# PreAmplifier.net
KiCad netlist of a schematic drawn in Altium Designer
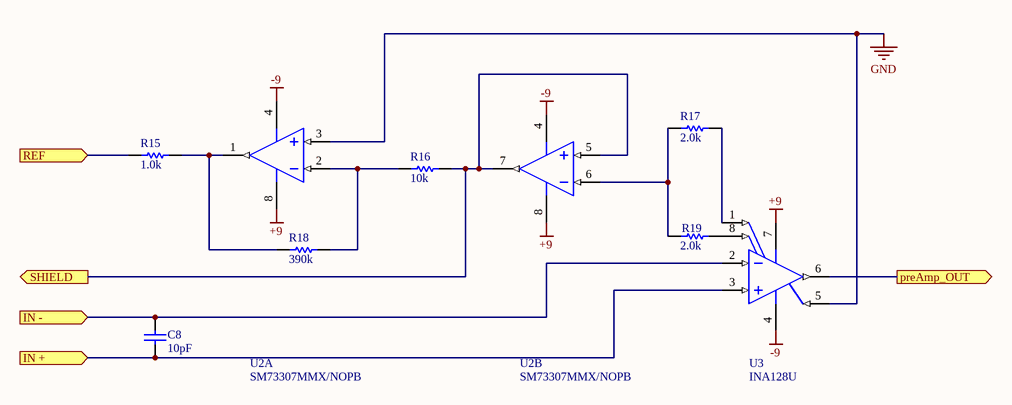
[diagram p0: PreAmplifier.SchDoc]

(export (version "E")
  (design (tool "Eeschema 10.0.6"))
  (components
    (comp (ref "C8")
      (value "10pF")
      (footprint "0402cap")
      (description "0402 Ceramic Chip Capacitor - Standard")
      (fields (field (name "Comment") "C0402"))
      (libsource (lib "Standard Components") (part "C0402"))
    )
    (comp (ref "R15")
      (value "1.0k")
      (footprint "0402RES")
      (description "0402 Chip Resistor - Standard")
      (fields (field (name "Comment") "R0402"))
      (libsource (lib "Standard Components") (part "R0402"))
    )
    (comp (ref "R16")
      (value "10k")
      (footprint "0402RES")
      (description "0402 Chip Resistor - Standard")
      (fields (field (name "Comment") "R0402"))
      (libsource (lib "Standard Components") (part "R0402"))
    )
    (comp (ref "R17")
      (value "2.0k")
      (footprint "0402RES")
      (description "0402 Chip Resistor - Standard")
      (fields (field (name "Comment") "R0402"))
      (libsource (lib "Standard Components") (part "R0402"))
    )
    (comp (ref "R18")
      (value "390k")
      (footprint "0402RES")
      (description "0402 Chip Resistor - Standard")
      (fields (field (name "Comment") "R0402"))
      (libsource (lib "Standard Components") (part "R0402"))
    )
    (comp (ref "R19")
      (value "2.0k")
      (footprint "0402RES")
      (description "0402 Chip Resistor - Standard")
      (fields (field (name "Comment") "R0402"))
      (libsource (lib "Standard Components") (part "R0402"))
    )
    (comp (ref "U2")
      (value "SM73307MMX/NOPB")
      (footprint "MUA08A_N")
      (description "Dual Precision, 17 MHz, Low Noise, CMOS Input Amplifier, 8-pin Mini SOIC, 3500 Reel")
      (fields (field (name "MANUFACTURER") "National Semiconductor"))
      (libsource (lib "National Semiconductor Amplifier") (part "SM73307MMX/NOPB"))
    )
    (comp (ref "U3")
      (value "INA128U")
      (footprint "TI-D8_N")
      (fields (field (name "MANUFACTURER") "Texas Instruments"))
      (libsource (lib "TI Amplifiers and Linear Instrumentation Amplifier") (part "INA128U"))
    )
  )
  (nets
    (net (code "1") (name "+9") (class "Default")
      (node (ref "U2") (pin "8") (pinfunction "V+_8") (pintype "power_in"))
      (node (ref "U3") (pin "7") (pinfunction "V+_7") (pintype "power_in"))
    )
    (net (code "2") (name "-9") (class "Default")
      (node (ref "U2") (pin "4") (pinfunction "V-_4") (pintype "power_in"))
      (node (ref "U3") (pin "4") (pinfunction "V-_4") (pintype "power_in"))
    )
    (net (code "3") (name "/IN +") (class "Default")
      (node (ref "C8") (pin "1") (pinfunction "1_1") (pintype "passive"))
      (node (ref "U3") (pin "3") (pinfunction "VIN+_3") (pintype "input"))
    )
    (net (code "4") (name "/IN -") (class "Default")
      (node (ref "C8") (pin "2") (pinfunction "2_2") (pintype "passive"))
      (node (ref "U3") (pin "2") (pinfunction "VIN-_2") (pintype "input"))
    )
    (net (code "5") (name "/REF") (class "Default")
      (node (ref "R15") (pin "1") (pinfunction "1_1") (pintype "passive"))
    )
    (net (code "6") (name "/SHIELD") (class "Default")
      (node (ref "R16") (pin "2") (pinfunction "2_2") (pintype "passive"))
      (node (ref "U2") (pin "5") (pinfunction "INB+_5") (pintype "input"))
      (node (ref "U2") (pin "7") (pinfunction "OUTB_7") (pintype "output"))
    )
    (net (code "7") (name "/preAmp_OUT") (class "Default")
      (node (ref "U3") (pin "6") (pinfunction "VO_6") (pintype "output"))
    )
    (net (code "8") (name "GND") (class "Default")
      (node (ref "U2") (pin "3") (pinfunction "INA+_3") (pintype "input"))
      (node (ref "U3") (pin "5") (pinfunction "REF_5") (pintype "input"))
    )
    (net (code "9") (name "Net-(R17-Pad2)") (class "Default")
      (node (ref "R17") (pin "2") (pinfunction "2_2") (pintype "passive"))
      (node (ref "U3") (pin "1") (pinfunction "RG_1") (pintype "input"))
    )
    (net (code "10") (name "Net-(R19-Pad2)") (class "Default")
      (node (ref "R19") (pin "2") (pinfunction "2_2") (pintype "passive"))
      (node (ref "U3") (pin "8") (pinfunction "RG_8") (pintype "input"))
    )
    (net (code "11") (name "Net-(U2A-INA-)") (class "Default")
      (node (ref "R16") (pin "1") (pinfunction "1_1") (pintype "passive"))
      (node (ref "R18") (pin "2") (pinfunction "2_2") (pintype "passive"))
      (node (ref "U2") (pin "2") (pinfunction "INA-_2") (pintype "input"))
    )
    (net (code "12") (name "Net-(U2A-OUTA)") (class "Default")
      (node (ref "R15") (pin "2") (pinfunction "2_2") (pintype "passive"))
      (node (ref "R18") (pin "1") (pinfunction "1_1") (pintype "passive"))
      (node (ref "U2") (pin "1") (pinfunction "OUTA_1") (pintype "output"))
    )
    (net (code "13") (name "Net-(U2B-INB-)") (class "Default")
      (node (ref "R17") (pin "1") (pinfunction "1_1") (pintype "passive"))
      (node (ref "R19") (pin "1") (pinfunction "1_1") (pintype "passive"))
      (node (ref "U2") (pin "6") (pinfunction "INB-_6") (pintype "input"))
    )
  )
)
